# ACmonitor.net
KiCad netlist of a schematic drawn in Altium Designer
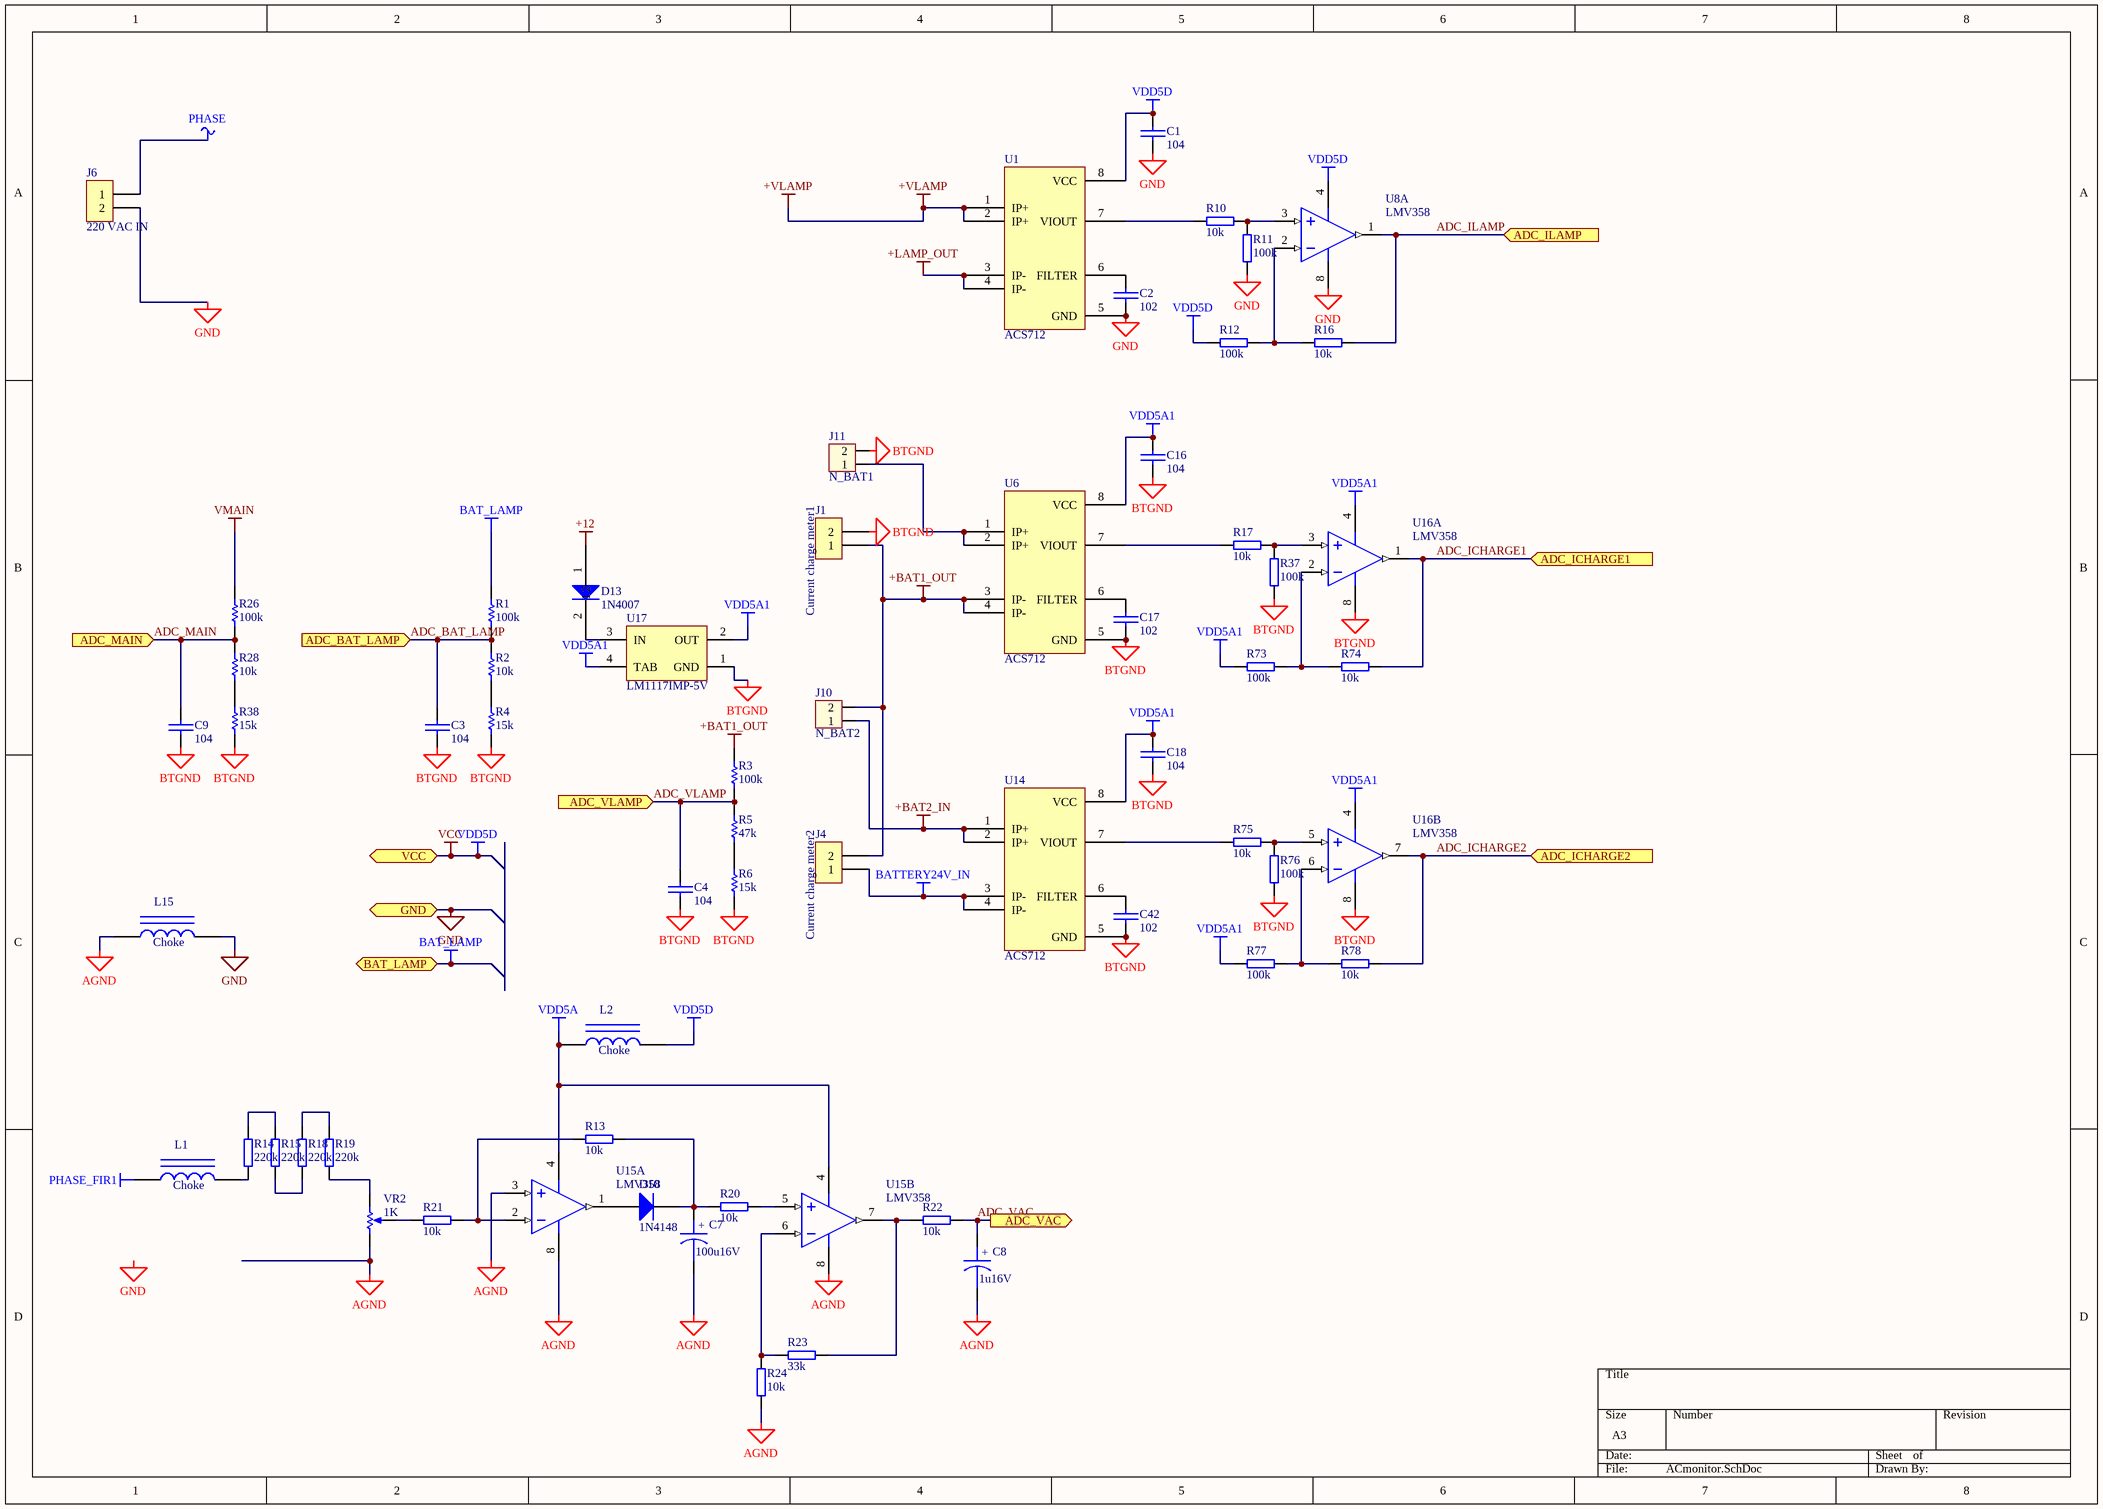
[diagram p0: ACmonitor.SchDoc]

(export (version "E")
  (design (tool "Eeschema 10.0.6"))
  (components
    (comp (ref "C1")
      (value "104")
      (footprint "C6-0805_N")
      (description "Capacitor")
      (libsource (lib "*") (part "CAP"))
    )
    (comp (ref "C2")
      (value "102")
      (footprint "C6-0805_N")
      (description "Capacitor")
      (libsource (lib "*") (part "CAP"))
    )
    (comp (ref "C3")
      (value "104")
      (footprint "C6-0805_N")
      (description "Capacitor")
      (libsource (lib "*") (part "CAP"))
    )
    (comp (ref "C4")
      (value "104")
      (footprint "C6-0805_N")
      (description "Capacitor")
      (libsource (lib "*") (part "CAP"))
    )
    (comp (ref "C7")
      (value "100u16V")
      (footprint "CAPMP7343X310N")
      (description "Capacitor")
      (libsource (lib "*") (part "CAPACITOR POL"))
    )
    (comp (ref "C8")
      (value "1u16V")
      (footprint "CAPMP3528X210N")
      (description "Capacitor")
      (libsource (lib "*") (part "CAPACITOR POL"))
    )
    (comp (ref "C9")
      (value "104")
      (footprint "C6-0805_N")
      (description "Capacitor")
      (libsource (lib "*") (part "CAP"))
    )
    (comp (ref "C16")
      (value "104")
      (footprint "C6-0805_N")
      (description "Capacitor")
      (libsource (lib "*") (part "CAP"))
    )
    (comp (ref "C17")
      (value "102")
      (footprint "C6-0805_N")
      (description "Capacitor")
      (libsource (lib "*") (part "CAP"))
    )
    (comp (ref "C18")
      (value "104")
      (footprint "C6-0805_N")
      (description "Capacitor")
      (libsource (lib "*") (part "CAP"))
    )
    (comp (ref "C42")
      (value "102")
      (footprint "C6-0805_N")
      (description "Capacitor")
      (libsource (lib "*") (part "CAP"))
    )
    (comp (ref "D10")
      (value "1N4148")
      (footprint "SOD80, LL-34")
      (description "1 Amp General Purpose Rectifier")
      (fields (field (name "PUBLISHER") "Altium Limited"))
      (libsource (lib "*") (part "Diode 1N4007"))
    )
    (comp (ref "D13") (value "1N4007") (footprint "DO-214AA") (libsource (lib "*") (part "DIODE")))
    (comp (ref "J1")
      (value "Current charge meter1")
      (footprint "TERMINAL2")
      (description "Connector")
      (libsource (lib "") (part "CON2_1"))
    )
    (comp (ref "J4")
      (value "Current charge meter2")
      (footprint "TERMINAL2")
      (description "Connector")
      (libsource (lib "") (part "CON2_1"))
    )
    (comp (ref "J6")
      (value "220 VAC IN")
      (footprint "TERMINAL2")
      (description "Connector")
      (libsource (lib "*") (part "CON2"))
    )
    (comp (ref "J10")
      (value "N_BAT2")
      (footprint "TERMINAL2")
      (description "Connector 2")
      (libsource (lib "syhaunguyen") (part "Con2"))
    )
    (comp (ref "J11")
      (value "N_BAT1")
      (footprint "TERMINAL2")
      (description "Connector 2")
      (libsource (lib "syhaunguyen") (part "Con2"))
    )
    (comp (ref "L1") (value "Choke") (footprint "R6-0805_N") (libsource (lib "*") (part "INDUCTOR IRON")))
    (comp (ref "L2") (value "Choke") (footprint "R6-0805_N") (libsource (lib "*") (part "INDUCTOR IRON")))
    (comp (ref "L15") (value "Choke") (footprint "R6-0805_N") (libsource (lib "*") (part "INDUCTOR IRON")))
    (comp (ref "R1")
      (value "100k")
      (footprint "6-0805_N")
      (description "Semiconductor Resistor")
      (fields (field (name "PUBLISHER") "*"))
      (libsource (lib "*") (part "Res Semi"))
    )
    (comp (ref "R2")
      (value "10k")
      (footprint "6-0805_N")
      (description "Semiconductor Resistor")
      (fields (field (name "PUBLISHER") "*"))
      (libsource (lib "*") (part "Res Semi"))
    )
    (comp (ref "R3")
      (value "100k")
      (footprint "6-0805_N")
      (description "Semiconductor Resistor")
      (fields (field (name "PUBLISHER") "*"))
      (libsource (lib "*") (part "Res Semi"))
    )
    (comp (ref "R4")
      (value "15k")
      (footprint "6-0805_N")
      (description "Semiconductor Resistor")
      (fields (field (name "PUBLISHER") "*"))
      (libsource (lib "*") (part "Res Semi"))
    )
    (comp (ref "R5")
      (value "47k")
      (footprint "6-0805_N")
      (description "Semiconductor Resistor")
      (fields (field (name "PUBLISHER") "*"))
      (libsource (lib "*") (part "Res Semi"))
    )
    (comp (ref "R6")
      (value "15k")
      (footprint "6-0805_N")
      (description "Semiconductor Resistor")
      (fields (field (name "PUBLISHER") "*"))
      (libsource (lib "*") (part "Res Semi"))
    )
    (comp (ref "R10") (value "10k") (footprint "6-0805_N") (libsource (lib "*") (part "RES2")))
    (comp (ref "R11") (value "100k") (footprint "6-0805_N") (libsource (lib "*") (part "RES2")))
    (comp (ref "R12") (value "100k") (footprint "6-0805_N") (libsource (lib "*") (part "RES2")))
    (comp (ref "R13") (value "10k") (footprint "6-0805_N") (libsource (lib "*") (part "RES2")))
    (comp (ref "R14") (value "220k") (footprint "R3216[1206]") (libsource (lib "*") (part "RES2")))
    (comp (ref "R15") (value "220k") (footprint "R3216[1206]") (libsource (lib "*") (part "RES2")))
    (comp (ref "R16") (value "10k") (footprint "6-0805_N") (libsource (lib "*") (part "RES2")))
    (comp (ref "R17") (value "10k") (footprint "6-0805_N") (libsource (lib "*") (part "RES2")))
    (comp (ref "R18") (value "220k") (footprint "R3216[1206]") (libsource (lib "*") (part "RES2")))
    (comp (ref "R19") (value "220k") (footprint "R3216[1206]") (libsource (lib "*") (part "RES2")))
    (comp (ref "R20") (value "10k") (footprint "6-0805_N") (libsource (lib "*") (part "RES2")))
    (comp (ref "R21") (value "10k") (footprint "6-0805_N") (libsource (lib "*") (part "RES2")))
    (comp (ref "R22") (value "10k") (footprint "6-0805_N") (libsource (lib "*") (part "RES2")))
    (comp (ref "R23") (value "33k") (footprint "6-0805_N") (libsource (lib "*") (part "RES2")))
    (comp (ref "R24") (value "10k") (footprint "6-0805_N") (libsource (lib "*") (part "RES2")))
    (comp (ref "R26")
      (value "100k")
      (footprint "6-0805_N")
      (description "Semiconductor Resistor")
      (fields (field (name "PUBLISHER") "*"))
      (libsource (lib "*") (part "Res Semi"))
    )
    (comp (ref "R28")
      (value "10k")
      (footprint "6-0805_N")
      (description "Semiconductor Resistor")
      (fields (field (name "PUBLISHER") "*"))
      (libsource (lib "*") (part "Res Semi"))
    )
    (comp (ref "R37") (value "100k") (footprint "6-0805_N") (libsource (lib "*") (part "RES2")))
    (comp (ref "R38")
      (value "15k")
      (footprint "6-0805_N")
      (description "Semiconductor Resistor")
      (fields (field (name "PUBLISHER") "*"))
      (libsource (lib "*") (part "Res Semi"))
    )
    (comp (ref "R73") (value "100k") (footprint "6-0805_N") (libsource (lib "*") (part "RES2")))
    (comp (ref "R74") (value "10k") (footprint "6-0805_N") (libsource (lib "*") (part "RES2")))
    (comp (ref "R75") (value "10k") (footprint "6-0805_N") (libsource (lib "*") (part "RES2")))
    (comp (ref "R76") (value "100k") (footprint "6-0805_N") (libsource (lib "*") (part "RES2")))
    (comp (ref "R77") (value "100k") (footprint "6-0805_N") (libsource (lib "*") (part "RES2")))
    (comp (ref "R78") (value "10k") (footprint "6-0805_N") (libsource (lib "*") (part "RES2")))
    (comp (ref "U1") (value "ACS712") (footprint "M08A_N") (libsource (lib "Schlib1") (part "ACS712")))
    (comp (ref "U6") (value "ACS712") (footprint "M08A_N") (libsource (lib "Schlib1") (part "ACS712")))
    (comp (ref "U8")
      (value "LMV358")
      (footprint "M08A_N")
      (description "Low Power Dual Operational Amplifier, 8-pin Narrow SOIC")
      (fields
        (field (name "PARTNUMBER") "LM358AM")
        (field (name "MANUFACTURER") "National Semiconductor")
        (field (name "PUBLISHER") "Altium Limited")
      )
      (libsource (lib "NSC Amplifier") (part "LM358AM"))
    )
    (comp (ref "U14") (value "ACS712") (footprint "M08A_N") (libsource (lib "Schlib1") (part "ACS712")))
    (comp (ref "U15")
      (value "LMV358")
      (footprint "M08A_N")
      (description "Low Power Dual Operational Amplifier, 8-pin Narrow SOIC")
      (fields
        (field (name "PARTNUMBER") "LM358AM")
        (field (name "MANUFACTURER") "National Semiconductor")
        (field (name "PUBLISHER") "Altium Limited")
      )
      (libsource (lib "NSC Amplifier") (part "LM358AM"))
    )
    (comp (ref "U16")
      (value "LMV358")
      (footprint "M08A_N")
      (description "Low Power Dual Operational Amplifier, 8-pin Narrow SOIC")
      (fields
        (field (name "PARTNUMBER") "LM358AM")
        (field (name "MANUFACTURER") "National Semiconductor")
        (field (name "PUBLISHER") "Altium Limited")
      )
      (libsource (lib "NSC Amplifier") (part "LM358AM"))
    )
    (comp (ref "U17")
      (value "LM1117IMP-5V")
      (footprint "MP04A_N")
      (description "800mA Low-Dropout Linear Regulator, 4-pin SOT-223")
      (fields
        (field (name "PARTNUMBER") "LM1117IMP-3.3")
        (field (name "MANUFACTURER") "National Semiconductor")
        (field (name "PUBLISHER") "Altium Limited")
      )
      (libsource (lib "NSC LDO") (part "LM1117IMP-3.3"))
    )
    (comp (ref "VR2")
      (value "1K")
      (footprint "BTXANH")
      (description "Potentiometer")
      (fields (field (name "PUBLISHER") "*"))
      (libsource (lib "*") (part "RPot"))
    )
  )
  (nets
    (net (code "1") (name "+12") (class "Default")
      (node (ref "D13") (pin "1") (pinfunction "1_1") (pintype "passive"))
    )
    (net (code "2") (name "+BAT1_OUT") (class "Default")
      (node (ref "J1") (pin "1") (pinfunction "1_1") (pintype "passive"))
      (node (ref "J10") (pin "2") (pinfunction "2_2") (pintype "passive"))
      (node (ref "J4") (pin "2") (pinfunction "2_2") (pintype "passive"))
      (node (ref "R3") (pin "1") (pinfunction "1_1") (pintype "passive"))
      (node (ref "U6") (pin "3") (pinfunction "IP-_3") (pintype "passive"))
      (node (ref "U6") (pin "4") (pinfunction "IP-_4") (pintype "passive"))
    )
    (net (code "3") (name "+BAT2_IN") (class "Default")
      (node (ref "J10") (pin "1") (pinfunction "1_1") (pintype "passive"))
      (node (ref "U14") (pin "1") (pinfunction "IP+_1") (pintype "passive"))
      (node (ref "U14") (pin "2") (pinfunction "IP+_2") (pintype "passive"))
    )
    (net (code "4") (name "+LAMP_OUT") (class "Default")
      (node (ref "U1") (pin "3") (pinfunction "IP-_3") (pintype "passive"))
      (node (ref "U1") (pin "4") (pinfunction "IP-_4") (pintype "passive"))
    )
    (net (code "5") (name "+VLAMP") (class "Default")
      (node (ref "U1") (pin "1") (pinfunction "IP+_1") (pintype "passive"))
      (node (ref "U1") (pin "2") (pinfunction "IP+_2") (pintype "passive"))
    )
    (net (code "6") (name "/ADC_BAT_LAMP") (class "Default")
      (node (ref "C3") (pin "1") (pinfunction "1_1") (pintype "passive"))
      (node (ref "R1") (pin "2") (pinfunction "2_2") (pintype "passive"))
      (node (ref "R2") (pin "1") (pinfunction "1_1") (pintype "passive"))
    )
    (net (code "7") (name "/ADC_ICHARGE1") (class "Default")
      (node (ref "R74") (pin "2") (pinfunction "2_2") (pintype "passive"))
      (node (ref "U16") (pin "1") (pinfunction "OUTA_1") (pintype "output"))
    )
    (net (code "8") (name "/ADC_ICHARGE2") (class "Default")
      (node (ref "R78") (pin "2") (pinfunction "2_2") (pintype "passive"))
      (node (ref "U16") (pin "7") (pinfunction "OUTB_7") (pintype "output"))
    )
    (net (code "9") (name "/ADC_ILAMP") (class "Default")
      (node (ref "R16") (pin "2") (pinfunction "2_2") (pintype "passive"))
      (node (ref "U8") (pin "1") (pinfunction "OUTA_1") (pintype "output"))
    )
    (net (code "10") (name "/ADC_MAIN") (class "Default")
      (node (ref "C9") (pin "1") (pinfunction "1_1") (pintype "passive"))
      (node (ref "R26") (pin "2") (pinfunction "2_2") (pintype "passive"))
      (node (ref "R28") (pin "1") (pinfunction "1_1") (pintype "passive"))
    )
    (net (code "11") (name "/ADC_VAC") (class "Default")
      (node (ref "C8") (pin "1") (pinfunction "1_1") (pintype "passive"))
      (node (ref "R22") (pin "1") (pinfunction "1_1") (pintype "passive"))
    )
    (net (code "12") (name "/ADC_VLAMP") (class "Default")
      (node (ref "C4") (pin "1") (pinfunction "1_1") (pintype "passive"))
      (node (ref "R3") (pin "2") (pinfunction "2_2") (pintype "passive"))
      (node (ref "R5") (pin "1") (pinfunction "1_1") (pintype "passive"))
    )
    (net (code "13") (name "AGND") (class "Default")
      (node (ref "C7") (pin "2") (pinfunction "2_2") (pintype "passive"))
      (node (ref "C8") (pin "2") (pinfunction "2_2") (pintype "passive"))
      (node (ref "L15") (pin "1") (pinfunction "1_1") (pintype "passive"))
      (node (ref "R24") (pin "2") (pinfunction "2_2") (pintype "passive"))
      (node (ref "U15") (pin "3") (pinfunction "INA+_3") (pintype "input"))
      (node (ref "U15") (pin "8") (pinfunction "V+_8") (pintype "power_in"))
      (node (ref "VR2") (pin "1") (pinfunction "TOP_1") (pintype "passive"))
    )
    (net (code "14") (name "BATTERY24V_IN") (class "Default")
      (node (ref "J4") (pin "1") (pinfunction "1_1") (pintype "passive"))
      (node (ref "U14") (pin "3") (pinfunction "IP-_3") (pintype "passive"))
      (node (ref "U14") (pin "4") (pinfunction "IP-_4") (pintype "passive"))
    )
    (net (code "15") (name "BAT_LAMP") (class "Default")
      (node (ref "R1") (pin "1") (pinfunction "1_1") (pintype "passive"))
    )
    (net (code "16") (name "BTGND") (class "Default")
      (node (ref "C16") (pin "2") (pinfunction "2_2") (pintype "passive"))
      (node (ref "C17") (pin "2") (pinfunction "2_2") (pintype "passive"))
      (node (ref "C18") (pin "2") (pinfunction "2_2") (pintype "passive"))
      (node (ref "C3") (pin "2") (pinfunction "2_2") (pintype "passive"))
      (node (ref "C4") (pin "2") (pinfunction "2_2") (pintype "passive"))
      (node (ref "C42") (pin "2") (pinfunction "2_2") (pintype "passive"))
      (node (ref "C9") (pin "2") (pinfunction "2_2") (pintype "passive"))
      (node (ref "J1") (pin "2") (pinfunction "2_2") (pintype "passive"))
      (node (ref "J11") (pin "2") (pinfunction "2_2") (pintype "passive"))
      (node (ref "R37") (pin "2") (pinfunction "2_2") (pintype "passive"))
      (node (ref "R38") (pin "2") (pinfunction "2_2") (pintype "passive"))
      (node (ref "R4") (pin "2") (pinfunction "2_2") (pintype "passive"))
      (node (ref "R6") (pin "2") (pinfunction "2_2") (pintype "passive"))
      (node (ref "R76") (pin "2") (pinfunction "2_2") (pintype "passive"))
      (node (ref "U14") (pin "5") (pinfunction "GND_5") (pintype "passive"))
      (node (ref "U16") (pin "8") (pinfunction "V+_8") (pintype "power_in"))
      (node (ref "U17") (pin "1") (pinfunction "GND_1") (pintype "power_in"))
      (node (ref "U6") (pin "5") (pinfunction "GND_5") (pintype "passive"))
    )
    (net (code "17") (name "GND") (class "Default")
      (node (ref "C1") (pin "2") (pinfunction "2_2") (pintype "passive"))
      (node (ref "C2") (pin "2") (pinfunction "2_2") (pintype "passive"))
      (node (ref "J6") (pin "2") (pinfunction "2_2") (pintype "passive"))
      (node (ref "L15") (pin "2") (pinfunction "2_2") (pintype "passive"))
      (node (ref "R11") (pin "2") (pinfunction "2_2") (pintype "passive"))
      (node (ref "U1") (pin "5") (pinfunction "GND_5") (pintype "passive"))
      (node (ref "U8") (pin "8") (pinfunction "V+_8") (pintype "power_in"))
    )
    (net (code "18") (name "Net-(D10-A)") (class "Default")
      (node (ref "D10") (pin "1") (pinfunction "A_1") (pintype "passive"))
      (node (ref "U15") (pin "1") (pinfunction "OUTA_1") (pintype "output"))
    )
    (net (code "19") (name "Net-(D10-K)") (class "Default")
      (node (ref "C7") (pin "1") (pinfunction "1_1") (pintype "passive"))
      (node (ref "D10") (pin "2") (pinfunction "K_2") (pintype "passive"))
      (node (ref "R13") (pin "1") (pinfunction "1_1") (pintype "passive"))
      (node (ref "R20") (pin "2") (pinfunction "2_2") (pintype "passive"))
    )
    (net (code "20") (name "Net-(J11-Pad1)") (class "Default")
      (node (ref "J11") (pin "1") (pinfunction "1_1") (pintype "passive"))
      (node (ref "U6") (pin "1") (pinfunction "IP+_1") (pintype "passive"))
      (node (ref "U6") (pin "2") (pinfunction "IP+_2") (pintype "passive"))
    )
    (net (code "21") (name "Net-(L1-Pad2)") (class "Default")
      (node (ref "L1") (pin "2") (pinfunction "2_2") (pintype "passive"))
      (node (ref "R14") (pin "2") (pinfunction "2_2") (pintype "passive"))
    )
    (net (code "22") (name "Net-(R2-Pad2)") (class "Default")
      (node (ref "R2") (pin "2") (pinfunction "2_2") (pintype "passive"))
      (node (ref "R4") (pin "1") (pinfunction "1_1") (pintype "passive"))
    )
    (net (code "23") (name "Net-(R5-Pad2)") (class "Default")
      (node (ref "R5") (pin "2") (pinfunction "2_2") (pintype "passive"))
      (node (ref "R6") (pin "1") (pinfunction "1_1") (pintype "passive"))
    )
    (net (code "24") (name "Net-(R14-Pad1)") (class "Default")
      (node (ref "R14") (pin "1") (pinfunction "1_1") (pintype "passive"))
      (node (ref "R15") (pin "1") (pinfunction "1_1") (pintype "passive"))
    )
    (net (code "25") (name "Net-(R15-Pad2)") (class "Default")
      (node (ref "R15") (pin "2") (pinfunction "2_2") (pintype "passive"))
      (node (ref "R18") (pin "2") (pinfunction "2_2") (pintype "passive"))
    )
    (net (code "26") (name "Net-(R18-Pad1)") (class "Default")
      (node (ref "R18") (pin "1") (pinfunction "1_1") (pintype "passive"))
      (node (ref "R19") (pin "1") (pinfunction "1_1") (pintype "passive"))
    )
    (net (code "27") (name "Net-(R28-Pad2)") (class "Default")
      (node (ref "R28") (pin "2") (pinfunction "2_2") (pintype "passive"))
      (node (ref "R38") (pin "1") (pinfunction "1_1") (pintype "passive"))
    )
    (net (code "28") (name "Net-(U1-FILTER)") (class "Default")
      (node (ref "C2") (pin "1") (pinfunction "1_1") (pintype "passive"))
      (node (ref "U1") (pin "6") (pinfunction "FILTER_6") (pintype "passive"))
    )
    (net (code "29") (name "Net-(U1-VIOUT)") (class "Default")
      (node (ref "R10") (pin "2") (pinfunction "2_2") (pintype "passive"))
      (node (ref "U1") (pin "7") (pinfunction "VIOUT_7") (pintype "passive"))
    )
    (net (code "30") (name "Net-(U6-FILTER)") (class "Default")
      (node (ref "C17") (pin "1") (pinfunction "1_1") (pintype "passive"))
      (node (ref "U6") (pin "6") (pinfunction "FILTER_6") (pintype "passive"))
    )
    (net (code "31") (name "Net-(U6-VIOUT)") (class "Default")
      (node (ref "R17") (pin "2") (pinfunction "2_2") (pintype "passive"))
      (node (ref "U6") (pin "7") (pinfunction "VIOUT_7") (pintype "passive"))
    )
    (net (code "32") (name "Net-(U8A-INA+)") (class "Default")
      (node (ref "R10") (pin "1") (pinfunction "1_1") (pintype "passive"))
      (node (ref "R11") (pin "1") (pinfunction "1_1") (pintype "passive"))
      (node (ref "U8") (pin "3") (pinfunction "INA+_3") (pintype "input"))
    )
    (net (code "33") (name "Net-(U8A-INA-)") (class "Default")
      (node (ref "R12") (pin "1") (pinfunction "1_1") (pintype "passive"))
      (node (ref "R16") (pin "1") (pinfunction "1_1") (pintype "passive"))
      (node (ref "U8") (pin "2") (pinfunction "INA-_2") (pintype "input"))
    )
    (net (code "34") (name "Net-(U14-FILTER)") (class "Default")
      (node (ref "C42") (pin "1") (pinfunction "1_1") (pintype "passive"))
      (node (ref "U14") (pin "6") (pinfunction "FILTER_6") (pintype "passive"))
    )
    (net (code "35") (name "Net-(U14-VIOUT)") (class "Default")
      (node (ref "R75") (pin "2") (pinfunction "2_2") (pintype "passive"))
      (node (ref "U14") (pin "7") (pinfunction "VIOUT_7") (pintype "passive"))
    )
    (net (code "36") (name "Net-(U15A-INA-)") (class "Default")
      (node (ref "R13") (pin "2") (pinfunction "2_2") (pintype "passive"))
      (node (ref "R21") (pin "1") (pinfunction "1_1") (pintype "passive"))
      (node (ref "U15") (pin "2") (pinfunction "INA-_2") (pintype "input"))
    )
    (net (code "37") (name "Net-(U15B-INB+)") (class "Default")
      (node (ref "R20") (pin "1") (pinfunction "1_1") (pintype "passive"))
      (node (ref "U15") (pin "5") (pinfunction "INB+_5") (pintype "input"))
    )
    (net (code "38") (name "Net-(U15B-INB-)") (class "Default")
      (node (ref "R23") (pin "2") (pinfunction "2_2") (pintype "passive"))
      (node (ref "R24") (pin "1") (pinfunction "1_1") (pintype "passive"))
      (node (ref "U15") (pin "6") (pinfunction "INB-_6") (pintype "input"))
    )
    (net (code "39") (name "Net-(U15B-OUTB)") (class "Default")
      (node (ref "R22") (pin "2") (pinfunction "2_2") (pintype "passive"))
      (node (ref "R23") (pin "1") (pinfunction "1_1") (pintype "passive"))
      (node (ref "U15") (pin "7") (pinfunction "OUTB_7") (pintype "output"))
    )
    (net (code "40") (name "Net-(U16A-INA+)") (class "Default")
      (node (ref "R17") (pin "1") (pinfunction "1_1") (pintype "passive"))
      (node (ref "R37") (pin "1") (pinfunction "1_1") (pintype "passive"))
      (node (ref "U16") (pin "3") (pinfunction "INA+_3") (pintype "input"))
    )
    (net (code "41") (name "Net-(U16A-INA-)") (class "Default")
      (node (ref "R73") (pin "1") (pinfunction "1_1") (pintype "passive"))
      (node (ref "R74") (pin "1") (pinfunction "1_1") (pintype "passive"))
      (node (ref "U16") (pin "2") (pinfunction "INA-_2") (pintype "input"))
    )
    (net (code "42") (name "Net-(U16B-INB+)") (class "Default")
      (node (ref "R75") (pin "1") (pinfunction "1_1") (pintype "passive"))
      (node (ref "R76") (pin "1") (pinfunction "1_1") (pintype "passive"))
      (node (ref "U16") (pin "5") (pinfunction "INB+_5") (pintype "input"))
    )
    (net (code "43") (name "Net-(U16B-INB-)") (class "Default")
      (node (ref "R77") (pin "1") (pinfunction "1_1") (pintype "passive"))
      (node (ref "R78") (pin "1") (pinfunction "1_1") (pintype "passive"))
      (node (ref "U16") (pin "6") (pinfunction "INB-_6") (pintype "input"))
    )
    (net (code "44") (name "Net-(U17-IN)") (class "Default")
      (node (ref "D13") (pin "2") (pinfunction "2_2") (pintype "passive"))
      (node (ref "U17") (pin "3") (pinfunction "IN_3") (pintype "power_in"))
    )
    (net (code "45") (name "Net-(VR2-BOT)") (class "Default")
      (node (ref "R19") (pin "2") (pinfunction "2_2") (pintype "passive"))
      (node (ref "VR2") (pin "3") (pinfunction "BOT_3") (pintype "passive"))
    )
    (net (code "46") (name "Net-(VR2-TAP)") (class "Default")
      (node (ref "R21") (pin "2") (pinfunction "2_2") (pintype "passive"))
      (node (ref "VR2") (pin "2") (pinfunction "TAP_2") (pintype "passive"))
    )
    (net (code "47") (name "PHASE") (class "Default")
      (node (ref "J6") (pin "1") (pinfunction "1_1") (pintype "passive"))
    )
    (net (code "48") (name "PHASE_FIR1") (class "Default")
      (node (ref "L1") (pin "1") (pinfunction "1_1") (pintype "passive"))
    )
    (net (code "49") (name "VCC") (class "Default")
      (node (ref "C1") (pin "1") (pinfunction "1_1") (pintype "passive"))
      (node (ref "L2") (pin "2") (pinfunction "2_2") (pintype "passive"))
      (node (ref "R12") (pin "2") (pinfunction "2_2") (pintype "passive"))
      (node (ref "U1") (pin "8") (pinfunction "VCC_8") (pintype "passive"))
      (node (ref "U8") (pin "4") (pinfunction "GND_4") (pintype "power_in"))
    )
    (net (code "50") (name "VDD5A") (class "Default")
      (node (ref "L2") (pin "1") (pinfunction "1_1") (pintype "passive"))
      (node (ref "U15") (pin "4") (pinfunction "GND_4") (pintype "power_in"))
    )
    (net (code "51") (name "VDD5A1") (class "Default")
      (node (ref "C16") (pin "1") (pinfunction "1_1") (pintype "passive"))
      (node (ref "C18") (pin "1") (pinfunction "1_1") (pintype "passive"))
      (node (ref "R73") (pin "2") (pinfunction "2_2") (pintype "passive"))
      (node (ref "R77") (pin "2") (pinfunction "2_2") (pintype "passive"))
      (node (ref "U14") (pin "8") (pinfunction "VCC_8") (pintype "passive"))
      (node (ref "U16") (pin "4") (pinfunction "GND_4") (pintype "power_in"))
      (node (ref "U17") (pin "2") (pinfunction "OUT_2") (pintype "power_in"))
      (node (ref "U17") (pin "4") (pinfunction "TAB_4") (pintype "power_in"))
      (node (ref "U6") (pin "8") (pinfunction "VCC_8") (pintype "passive"))
    )
    (net (code "52") (name "VMAIN") (class "Default")
      (node (ref "R26") (pin "1") (pinfunction "1_1") (pintype "passive"))
    )
  )
)
